# openSX70_ALADDIN_V391C_20180205.net
KiCad netlist of a schematic drawn in EAGLE
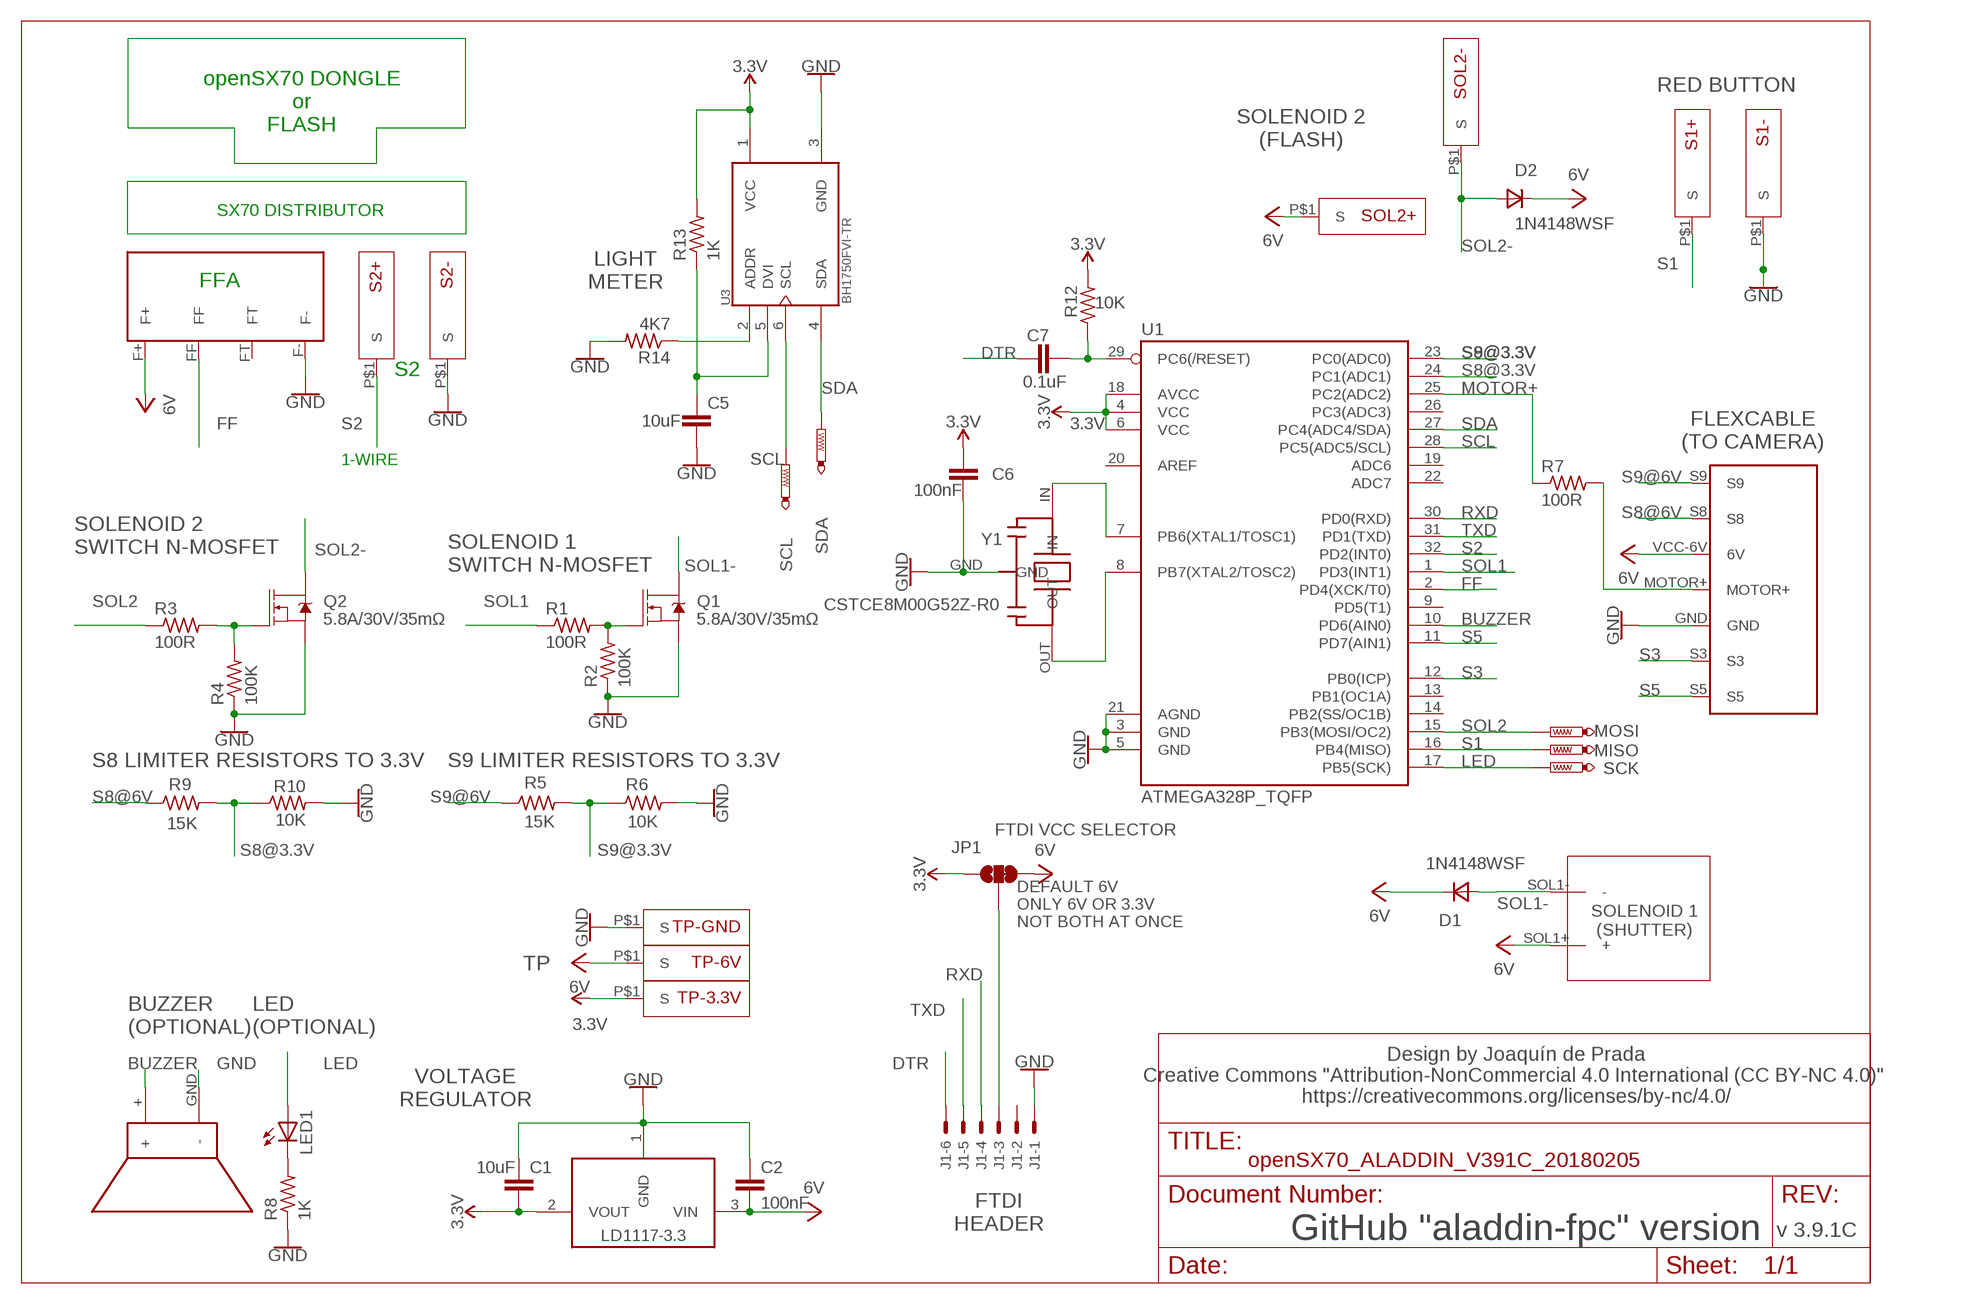
[diagram p0: schematic, sheet 1]

(export (version "E")
  (design (tool "Eeschema 10.0.6"))
  (components
    (comp (ref "BUZZ1")
      (value "CSET8-5G")
      (footprint "eagle-import:CSET8-5G_PACKAGE")
      (libsource (lib "eagle-import") (part "CSET8-5G"))
    )
    (comp (ref "C1")
      (value "10uF")
      (footprint "eagle-import:0603")
      (libsource (lib "eagle-import") (part "10UF-0603-6.3V-20%"))
    )
    (comp (ref "C2")
      (value "100nF")
      (footprint "eagle-import:C0603K")
      (libsource (lib "eagle-import") (part "C-EUC0603K"))
    )
    (comp (ref "C5")
      (value "10uF")
      (footprint "eagle-import:0603")
      (libsource (lib "eagle-import") (part "10UF-0603-6.3V-20%"))
    )
    (comp (ref "C6")
      (value "100nF")
      (footprint "eagle-import:C0603")
      (libsource (lib "eagle-import") (part "C-EUC0603"))
    )
    (comp (ref "C7")
      (value "0.1uF")
      (footprint "eagle-import:0603")
      (libsource (lib "eagle-import") (part "0.1UF-0603-25V-(+80/-20%)"))
    )
    (comp (ref "D1")
      (value "1N4148WSF")
      (footprint "eagle-import:SOD323")
      (fields (field (name "MPN") "CDSOD323-T05C"))
      (libsource (lib "eagle-import") (part "DSOD323"))
    )
    (comp (ref "D2")
      (value "1N4148WSF")
      (footprint "eagle-import:SOD323")
      (fields (field (name "MPN") "CDSOD323-T05C"))
      (libsource (lib "eagle-import") (part "DSOD323"))
    )
    (comp (ref "J1")
      (value "GND")
      (footprint "eagle-import:XF2L-0625-1")
      (fields (field (name "MF") "OMRON COMPONENTS USA") (field (name "MPN") "XF2L-0625-1"))
      (libsource (lib "eagle-import") (part "XF2-06?25-1L"))
    )
    (comp (ref "JP1")
      (value "FTDI VCC SELECTOR")
      (footprint "eagle-import:SMT-JUMPER_3_1-NC_TRACE_SILK")
      (libsource (lib "eagle-import") (part "JUMPER-SMT_3_1-NC_TRACE_SILK"))
    )
    (comp (ref "LD11172.5V")
      (value "LD1117 2.5V")
      (footprint "eagle-import:SOT223")
      (fields (field (name "MF") "Advanced Monolithic Systems") (field (name "MP") "AMS1117-5.0"))
      (libsource (lib "eagle-import") (part "LD1117-3.3"))
    )
    (comp (ref "LED1")
      (value "LEDCHIPLED_0805")
      (footprint "eagle-import:CHIPLED_0805")
      (libsource (lib "eagle-import") (part "LEDCHIPLED_0805"))
    )
    (comp (ref "MISO")
      (value "PTR1TP08R")
      (footprint "eagle-import:TP08R")
      (libsource (lib "eagle-import") (part "PTR1TP08R"))
    )
    (comp (ref "MOSI")
      (value "PTR1TP08R")
      (footprint "eagle-import:TP08R")
      (libsource (lib "eagle-import") (part "PTR1TP08R"))
    )
    (comp (ref "Q1")
      (value "5.8A/30V/35mΩ")
      (footprint "eagle-import:SOT23-3")
      (libsource (lib "eagle-import") (part "MOSFET-NCH-AO3404A"))
    )
    (comp (ref "Q2")
      (value "5.8A/30V/35mΩ")
      (footprint "eagle-import:SOT23-3")
      (libsource (lib "eagle-import") (part "MOSFET-NCH-AO3404A"))
    )
    (comp (ref "R1")
      (value "100R")
      (footprint "eagle-import:R0603")
      (libsource (lib "eagle-import") (part "R-US_R0603"))
    )
    (comp (ref "R2")
      (value "100K")
      (footprint "eagle-import:R0603")
      (libsource (lib "eagle-import") (part "R-US_R0603"))
    )
    (comp (ref "R3")
      (value "100R")
      (footprint "eagle-import:R0603")
      (libsource (lib "eagle-import") (part "R-US_R0603"))
    )
    (comp (ref "R4")
      (value "100K")
      (footprint "eagle-import:R0603")
      (libsource (lib "eagle-import") (part "R-US_R0603"))
    )
    (comp (ref "R5")
      (value "15K")
      (footprint "eagle-import:R0603")
      (libsource (lib "eagle-import") (part "R-US_R0603"))
    )
    (comp (ref "R6")
      (value "10K")
      (footprint "eagle-import:R0603")
      (libsource (lib "eagle-import") (part "R-US_R0603"))
    )
    (comp (ref "R7")
      (value "100R")
      (footprint "eagle-import:R0603")
      (libsource (lib "eagle-import") (part "R-US_R0603"))
    )
    (comp (ref "R8")
      (value "1K")
      (footprint "eagle-import:R0603")
      (libsource (lib "eagle-import") (part "R-US_R0603"))
    )
    (comp (ref "R9")
      (value "15K")
      (footprint "eagle-import:R0603")
      (libsource (lib "eagle-import") (part "R-US_R0603"))
    )
    (comp (ref "R10")
      (value "10K")
      (footprint "eagle-import:R0603")
      (libsource (lib "eagle-import") (part "R-US_R0603"))
    )
    (comp (ref "R12")
      (value "10K")
      (footprint "eagle-import:R0603")
      (libsource (lib "eagle-import") (part "R-US_R0603"))
    )
    (comp (ref "R13")
      (value "1K")
      (footprint "eagle-import:R0603")
      (libsource (lib "eagle-import") (part "R-US_R0603"))
    )
    (comp (ref "R14")
      (value "4K7")
      (footprint "eagle-import:R0603")
      (libsource (lib "eagle-import") (part "R-US_R0603"))
    )
    (comp (ref "S1+")
      (value "SX70-S-PAD-NEW")
      (footprint "eagle-import:SX70-S-PAD2")
      (libsource (lib "eagle-import") (part "SX70-S-PAD-NEW"))
    )
    (comp (ref "S1-")
      (value "SX70-S-PAD-NEW")
      (footprint "eagle-import:SX70-S-PAD2")
      (libsource (lib "eagle-import") (part "SX70-S-PAD-NEW"))
    )
    (comp (ref "S2+")
      (value "SX70-S-PAD-NEW")
      (footprint "eagle-import:SX70-S-PAD2")
      (libsource (lib "eagle-import") (part "SX70-S-PAD-NEW"))
    )
    (comp (ref "S2-")
      (value "SX70-S-PAD-NEW")
      (footprint "eagle-import:SX70-S-PAD2")
      (libsource (lib "eagle-import") (part "SX70-S-PAD-NEW"))
    )
    (comp (ref "SCK")
      (value "PTR1TP08R")
      (footprint "eagle-import:TP08R")
      (libsource (lib "eagle-import") (part "PTR1TP08R"))
    )
    (comp (ref "SCL")
      (value "PTR1TP08R")
      (footprint "eagle-import:TP08R")
      (libsource (lib "eagle-import") (part "PTR1TP08R"))
    )
    (comp (ref "SDA")
      (value "PTR1TP08R")
      (footprint "eagle-import:TP08R")
      (libsource (lib "eagle-import") (part "PTR1TP08R"))
    )
    (comp (ref "SOL1")
      (value "SX70-SOLENOID1-2PADS")
      (footprint "eagle-import:SX70-SOLENOID1-2")
      (libsource (lib "eagle-import") (part "SX70-SOLENOID1-2PADS"))
    )
    (comp (ref "SOL2+")
      (value "SX70-S-PAD-NEW")
      (footprint "eagle-import:SX70-S-PAD2")
      (libsource (lib "eagle-import") (part "SX70-S-PAD-NEW"))
    )
    (comp (ref "SOL2-")
      (value "SX70-S-PAD-NEW")
      (footprint "eagle-import:SX70-S-PAD2")
      (libsource (lib "eagle-import") (part "SX70-S-PAD-NEW"))
    )
    (comp (ref "TP-3.3V")
      (value "SX70-S-PAD-NEW")
      (footprint "eagle-import:SX70-S-PAD2")
      (libsource (lib "eagle-import") (part "SX70-S-PAD-NEW"))
    )
    (comp (ref "TP-6V")
      (value "SX70-S-PAD-NEW")
      (footprint "eagle-import:SX70-S-PAD2")
      (libsource (lib "eagle-import") (part "SX70-S-PAD-NEW"))
    )
    (comp (ref "TP-GND")
      (value "SX70-S-PAD-NEW")
      (footprint "eagle-import:SX70-S-PAD2")
      (libsource (lib "eagle-import") (part "SX70-S-PAD-NEW"))
    )
    (comp (ref "U$1")
      (value "SX70-7-PAD")
      (footprint "eagle-import:SX70-7-PAD")
      (libsource (lib "eagle-import") (part "SX70-7-PAD"))
    )
    (comp (ref "U$2")
      (value "FFA")
      (footprint "eagle-import:FFA-PAD-PACKAGE")
      (libsource (lib "eagle-import") (part "SX70-FFA-PAD"))
    )
    (comp (ref "U1")
      (value "ATMEGA328P_TQFP")
      (footprint "eagle-import:TQFP32-08")
      (libsource (lib "eagle-import") (part "ATMEGA328P_TQFP"))
    )
    (comp (ref "U3")
      (value "BH1750FVI-TR")
      (footprint "eagle-import:SOTFL50P300X75-6N")
      (fields (field (name "MF") "Rohm"))
      (libsource (lib "eagle-import") (part "BH1750FVI-TR"))
    )
    (comp (ref "Y1")
      (value "CSTCE8M00G52Z-R0")
      (footprint "eagle-import:CFP95P160X100-3N")
      (fields (field (name "MF") "Murata") (field (name "MP") "CSTCE16M0V53-R0"))
      (libsource (lib "eagle-import") (part "CSTCE16M0V53-R0"))
    )
  )
  (nets
    (net (code "1") (name "/BUZZER") (class "Default")
      (node (ref "BUZZ1") (pin "+") (pinfunction "+_+") (pintype "bidirectional"))
      (node (ref "U1") (pin "10") (pinfunction "PD6(AIN0)_10") (pintype "bidirectional"))
    )
    (net (code "2") (name "/DTR") (class "Default")
      (node (ref "C7") (pin "1") (pinfunction "1_1") (pintype "passive"))
      (node (ref "J1") (pin "6") (pinfunction "MS_6") (pintype "passive"))
    )
    (net (code "3") (name "/FF") (class "Default")
      (node (ref "U$2") (pin "FF") (pinfunction "FF_FF") (pintype "bidirectional"))
      (node (ref "U1") (pin "2") (pinfunction "PD4(XCK/T0)_2") (pintype "bidirectional"))
    )
    (net (code "4") (name "/LED") (class "Default")
      (node (ref "LED1") (pin "A") (pinfunction "A_A") (pintype "passive"))
      (node (ref "SCK") (pin "TP") (pinfunction "TP_TP") (pintype "input"))
      (node (ref "U1") (pin "17") (pinfunction "PB5(SCK)_17") (pintype "bidirectional"))
    )
    (net (code "5") (name "/MOTOR+") (class "Default")
      (node (ref "R7") (pin "1") (pinfunction "1_1") (pintype "passive"))
      (node (ref "U1") (pin "25") (pinfunction "PC2(ADC2)_25") (pintype "bidirectional"))
    )
    (net (code "6") (name "/RXD") (class "Default")
      (node (ref "J1") (pin "4") (pinfunction "MS_4") (pintype "passive"))
      (node (ref "U1") (pin "30") (pinfunction "PD0(RXD)_30") (pintype "bidirectional"))
    )
    (net (code "7") (name "/S1") (class "Default")
      (node (ref "MISO") (pin "TP") (pinfunction "TP_TP") (pintype "input"))
      (node (ref "S1+") (pin "P$1") (pinfunction "S_P$1") (pintype "bidirectional"))
      (node (ref "U1") (pin "16") (pinfunction "PB4(MISO)_16") (pintype "bidirectional"))
    )
    (net (code "8") (name "/S2") (class "Default")
      (node (ref "S2+") (pin "P$1") (pinfunction "S_P$1") (pintype "bidirectional"))
      (node (ref "U1") (pin "32") (pinfunction "PD2(INT0)_32") (pintype "bidirectional"))
    )
    (net (code "9") (name "/S3") (class "Default")
      (node (ref "U$1") (pin "S3") (pinfunction "S3_S3") (pintype "bidirectional"))
      (node (ref "U1") (pin "12") (pinfunction "PB0(ICP)_12") (pintype "bidirectional"))
    )
    (net (code "10") (name "/S5") (class "Default")
      (node (ref "U$1") (pin "S5") (pinfunction "S5_S5") (pintype "bidirectional"))
      (node (ref "U1") (pin "11") (pinfunction "PD7(AIN1)_11") (pintype "bidirectional"))
    )
    (net (code "11") (name "/S8@3.3V") (class "Default")
      (node (ref "R10") (pin "1") (pinfunction "1_1") (pintype "passive"))
      (node (ref "R9") (pin "2") (pinfunction "2_2") (pintype "passive"))
      (node (ref "U1") (pin "24") (pinfunction "PC1(ADC1)_24") (pintype "bidirectional"))
    )
    (net (code "12") (name "/S8@6V") (class "Default")
      (node (ref "R9") (pin "1") (pinfunction "1_1") (pintype "passive"))
      (node (ref "U$1") (pin "S8") (pinfunction "S8_S8") (pintype "bidirectional"))
    )
    (net (code "13") (name "/S9@3.3V") (class "Default")
      (node (ref "R5") (pin "2") (pinfunction "2_2") (pintype "passive"))
      (node (ref "R6") (pin "1") (pinfunction "1_1") (pintype "passive"))
      (node (ref "U1") (pin "23") (pinfunction "PC0(ADC0)_23") (pintype "bidirectional"))
    )
    (net (code "14") (name "/S9@6V") (class "Default")
      (node (ref "R5") (pin "1") (pinfunction "1_1") (pintype "passive"))
      (node (ref "U$1") (pin "S9") (pinfunction "S9_S9") (pintype "bidirectional"))
    )
    (net (code "15") (name "/SCL") (class "Default")
      (node (ref "SCL") (pin "TP") (pinfunction "TP_TP") (pintype "input"))
      (node (ref "U1") (pin "28") (pinfunction "PC5(ADC5/SCL)_28") (pintype "bidirectional"))
      (node (ref "U3") (pin "6") (pinfunction "SCL_6") (pintype "input"))
    )
    (net (code "16") (name "/SDA") (class "Default")
      (node (ref "SDA") (pin "TP") (pinfunction "TP_TP") (pintype "input"))
      (node (ref "U1") (pin "27") (pinfunction "PC4(ADC4/SDA)_27") (pintype "bidirectional"))
      (node (ref "U3") (pin "4") (pinfunction "SDA_4") (pintype "bidirectional"))
    )
    (net (code "17") (name "/SOL1") (class "Default")
      (node (ref "R1") (pin "1") (pinfunction "1_1") (pintype "passive"))
      (node (ref "U1") (pin "1") (pinfunction "PD3(INT1)_1") (pintype "bidirectional"))
    )
    (net (code "18") (name "/SOL1-") (class "Default")
      (node (ref "D1") (pin "2") (pinfunction "A_2") (pintype "passive"))
      (node (ref "Q1") (pin "3") (pinfunction "D_3") (pintype "bidirectional"))
      (node (ref "SOL1") (pin "SOL1-") (pinfunction "-_SOL1-") (pintype "bidirectional"))
    )
    (net (code "19") (name "/SOL2") (class "Default")
      (node (ref "MOSI") (pin "TP") (pinfunction "TP_TP") (pintype "input"))
      (node (ref "R3") (pin "1") (pinfunction "1_1") (pintype "passive"))
      (node (ref "U1") (pin "15") (pinfunction "PB3(MOSI/OC2)_15") (pintype "bidirectional"))
    )
    (net (code "20") (name "/SOL2-") (class "Default")
      (node (ref "D2") (pin "2") (pinfunction "A_2") (pintype "passive"))
      (node (ref "Q2") (pin "3") (pinfunction "D_3") (pintype "bidirectional"))
      (node (ref "SOL2-") (pin "P$1") (pinfunction "S_P$1") (pintype "bidirectional"))
    )
    (net (code "21") (name "/TXD") (class "Default")
      (node (ref "J1") (pin "5") (pinfunction "MS_5") (pintype "passive"))
      (node (ref "U1") (pin "31") (pinfunction "PD1(TXD)_31") (pintype "bidirectional"))
    )
    (net (code "22") (name "3.3V") (class "Default")
      (node (ref "C1") (pin "2") (pinfunction "2_2") (pintype "passive"))
      (node (ref "C6") (pin "1") (pinfunction "1_1") (pintype "passive"))
      (node (ref "JP1") (pin "1") (pinfunction "1_1") (pintype "passive"))
      (node (ref "LD11172.5V") (pin "2") (pinfunction "VOUT_2") (pintype "bidirectional"))
      (node (ref "R12") (pin "2") (pinfunction "2_2") (pintype "passive"))
      (node (ref "R13") (pin "2") (pinfunction "2_2") (pintype "passive"))
      (node (ref "TP-3.3V") (pin "P$1") (pinfunction "S_P$1") (pintype "bidirectional"))
      (node (ref "U1") (pin "18") (pinfunction "AVCC_18") (pintype "bidirectional"))
      (node (ref "U1") (pin "4") (pinfunction "VCC_4") (pintype "bidirectional"))
      (node (ref "U1") (pin "6") (pinfunction "VCC_6") (pintype "bidirectional"))
      (node (ref "U3") (pin "1") (pinfunction "VCC_1") (pintype "power_in"))
    )
    (net (code "23") (name "6V") (class "Default")
      (node (ref "C2") (pin "2") (pinfunction "2_2") (pintype "passive"))
      (node (ref "D1") (pin "1") (pinfunction "C_1") (pintype "passive"))
      (node (ref "D2") (pin "1") (pinfunction "C_1") (pintype "passive"))
      (node (ref "JP1") (pin "3") (pinfunction "3_3") (pintype "passive"))
      (node (ref "LD11172.5V") (pin "3") (pinfunction "VIN_3") (pintype "bidirectional"))
      (node (ref "SOL1") (pin "SOL1+") (pinfunction "+_SOL1+") (pintype "bidirectional"))
      (node (ref "SOL2+") (pin "P$1") (pinfunction "S_P$1") (pintype "bidirectional"))
      (node (ref "TP-6V") (pin "P$1") (pinfunction "S_P$1") (pintype "bidirectional"))
      (node (ref "U$1") (pin "VCC-6V") (pinfunction "6V_VCC-6V") (pintype "bidirectional"))
      (node (ref "U$2") (pin "F+") (pinfunction "F+_F+") (pintype "bidirectional"))
    )
    (net (code "24") (name "GND") (class "Default")
      (node (ref "BUZZ1") (pin "GND") (pinfunction "-_GND") (pintype "bidirectional"))
      (node (ref "C1") (pin "1") (pinfunction "1_1") (pintype "passive"))
      (node (ref "C2") (pin "1") (pinfunction "1_1") (pintype "passive"))
      (node (ref "C5") (pin "2") (pinfunction "2_2") (pintype "passive"))
      (node (ref "C6") (pin "2") (pinfunction "2_2") (pintype "passive"))
      (node (ref "J1") (pin "1") (pinfunction "MS_1") (pintype "passive"))
      (node (ref "LD11172.5V") (pin "1") (pinfunction "GND_1") (pintype "bidirectional"))
      (node (ref "Q1") (pin "2") (pinfunction "S_2") (pintype "bidirectional"))
      (node (ref "Q2") (pin "2") (pinfunction "S_2") (pintype "bidirectional"))
      (node (ref "R10") (pin "2") (pinfunction "2_2") (pintype "passive"))
      (node (ref "R14") (pin "2") (pinfunction "2_2") (pintype "passive"))
      (node (ref "R2") (pin "1") (pinfunction "1_1") (pintype "passive"))
      (node (ref "R4") (pin "1") (pinfunction "1_1") (pintype "passive"))
      (node (ref "R6") (pin "2") (pinfunction "2_2") (pintype "passive"))
      (node (ref "R8") (pin "1") (pinfunction "1_1") (pintype "passive"))
      (node (ref "S1-") (pin "P$1") (pinfunction "S_P$1") (pintype "bidirectional"))
      (node (ref "S2-") (pin "P$1") (pinfunction "S_P$1") (pintype "bidirectional"))
      (node (ref "TP-GND") (pin "P$1") (pinfunction "S_P$1") (pintype "bidirectional"))
      (node (ref "U$1") (pin "GND") (pinfunction "GND_GND") (pintype "bidirectional"))
      (node (ref "U$2") (pin "F-") (pinfunction "F-_F-") (pintype "bidirectional"))
      (node (ref "U1") (pin "21") (pinfunction "AGND_21") (pintype "bidirectional"))
      (node (ref "U1") (pin "3") (pinfunction "GND_3") (pintype "bidirectional"))
      (node (ref "U1") (pin "5") (pinfunction "GND_5") (pintype "bidirectional"))
      (node (ref "U3") (pin "3") (pinfunction "GND_3") (pintype "power_in"))
      (node (ref "Y1") (pin "GND") (pinfunction "GND_GND") (pintype "passive"))
    )
    (net (code "25") (name "Net-(J1C-MS)") (class "Default")
      (node (ref "J1") (pin "3") (pinfunction "MS_3") (pintype "passive"))
      (node (ref "JP1") (pin "2") (pinfunction "2_2") (pintype "passive"))
    )
    (net (code "26") (name "Net-(LED1-PadC)") (class "Default")
      (node (ref "LED1") (pin "C") (pinfunction "C_C") (pintype "passive"))
      (node (ref "R8") (pin "2") (pinfunction "2_2") (pintype "passive"))
    )
    (net (code "27") (name "Net-(Q1-G)") (class "Default")
      (node (ref "Q1") (pin "1") (pinfunction "G_1") (pintype "bidirectional"))
      (node (ref "R1") (pin "2") (pinfunction "2_2") (pintype "passive"))
      (node (ref "R2") (pin "2") (pinfunction "2_2") (pintype "passive"))
    )
    (net (code "28") (name "Net-(Q2-G)") (class "Default")
      (node (ref "Q2") (pin "1") (pinfunction "G_1") (pintype "bidirectional"))
      (node (ref "R3") (pin "2") (pinfunction "2_2") (pintype "passive"))
      (node (ref "R4") (pin "2") (pinfunction "2_2") (pintype "passive"))
    )
    (net (code "29") (name "Net-(R7-Pad2)") (class "Default")
      (node (ref "R7") (pin "2") (pinfunction "2_2") (pintype "passive"))
      (node (ref "U$1") (pin "MOTOR+") (pinfunction "MOTOR+_MOTOR+") (pintype "bidirectional"))
    )
    (net (code "30") (name "Net-(U1-PB6(XTAL1{slash}TOSC1))") (class "Default")
      (node (ref "U1") (pin "7") (pinfunction "PB6(XTAL1/TOSC1)_7") (pintype "bidirectional"))
      (node (ref "Y1") (pin "IN") (pinfunction "IN_IN") (pintype "input"))
    )
    (net (code "31") (name "Net-(U1-PB7(XTAL2{slash}TOSC2))") (class "Default")
      (node (ref "U1") (pin "8") (pinfunction "PB7(XTAL2/TOSC2)_8") (pintype "bidirectional"))
      (node (ref "Y1") (pin "OUT") (pinfunction "OUT_OUT") (pintype "output"))
    )
    (net (code "32") (name "Net-(U1-PC6({slash}RESET))") (class "Default")
      (node (ref "C7") (pin "2") (pinfunction "2_2") (pintype "passive"))
      (node (ref "R12") (pin "1") (pinfunction "1_1") (pintype "passive"))
      (node (ref "U1") (pin "29") (pinfunction "PC6(/RESET)_29") (pintype "bidirectional"))
    )
    (net (code "33") (name "Net-(U3-ADDR)") (class "Default")
      (node (ref "R14") (pin "1") (pinfunction "1_1") (pintype "passive"))
      (node (ref "U3") (pin "2") (pinfunction "ADDR_2") (pintype "input"))
    )
    (net (code "34") (name "Net-(U3-DVI)") (class "Default")
      (node (ref "C5") (pin "1") (pinfunction "1_1") (pintype "passive"))
      (node (ref "R13") (pin "1") (pinfunction "1_1") (pintype "passive"))
      (node (ref "U3") (pin "5") (pinfunction "DVI_5") (pintype "input"))
    )
    (net (code "35") (name "unconnected-(J1B-MS-Pad2)") (class "Default")
      (node (ref "J1") (pin "2") (pinfunction "MS_2") (pintype "passive"))
    )
    (net (code "36") (name "unconnected-(U$2-PadFT)") (class "Default")
      (node (ref "U$2") (pin "FT") (pinfunction "FT_FT") (pintype "bidirectional"))
    )
    (net (code "37") (name "unconnected-(U1-ADC6-Pad19)") (class "Default")
      (node (ref "U1") (pin "19") (pinfunction "ADC6_19") (pintype "bidirectional"))
    )
    (net (code "38") (name "unconnected-(U1-ADC7-Pad22)") (class "Default")
      (node (ref "U1") (pin "22") (pinfunction "ADC7_22") (pintype "bidirectional"))
    )
    (net (code "39") (name "unconnected-(U1-AREF-Pad20)") (class "Default")
      (node (ref "U1") (pin "20") (pinfunction "AREF_20") (pintype "bidirectional"))
    )
    (net (code "40") (name "unconnected-(U1-PB1(OC1A)-Pad13)") (class "Default")
      (node (ref "U1") (pin "13") (pinfunction "PB1(OC1A)_13") (pintype "bidirectional"))
    )
    (net (code "41") (name "unconnected-(U1-PB2(SS{slash}OC1B)-Pad14)") (class "Default")
      (node (ref "U1") (pin "14") (pinfunction "PB2(SS/OC1B)_14") (pintype "bidirectional"))
    )
    (net (code "42") (name "unconnected-(U1-PC3(ADC3)-Pad26)") (class "Default")
      (node (ref "U1") (pin "26") (pinfunction "PC3(ADC3)_26") (pintype "bidirectional"))
    )
    (net (code "43") (name "unconnected-(U1-PD5(T1)-Pad9)") (class "Default")
      (node (ref "U1") (pin "9") (pinfunction "PD5(T1)_9") (pintype "bidirectional"))
    )
  )
)
